# STM32F103.net
KiCad netlist of a schematic drawn in Altium Designer
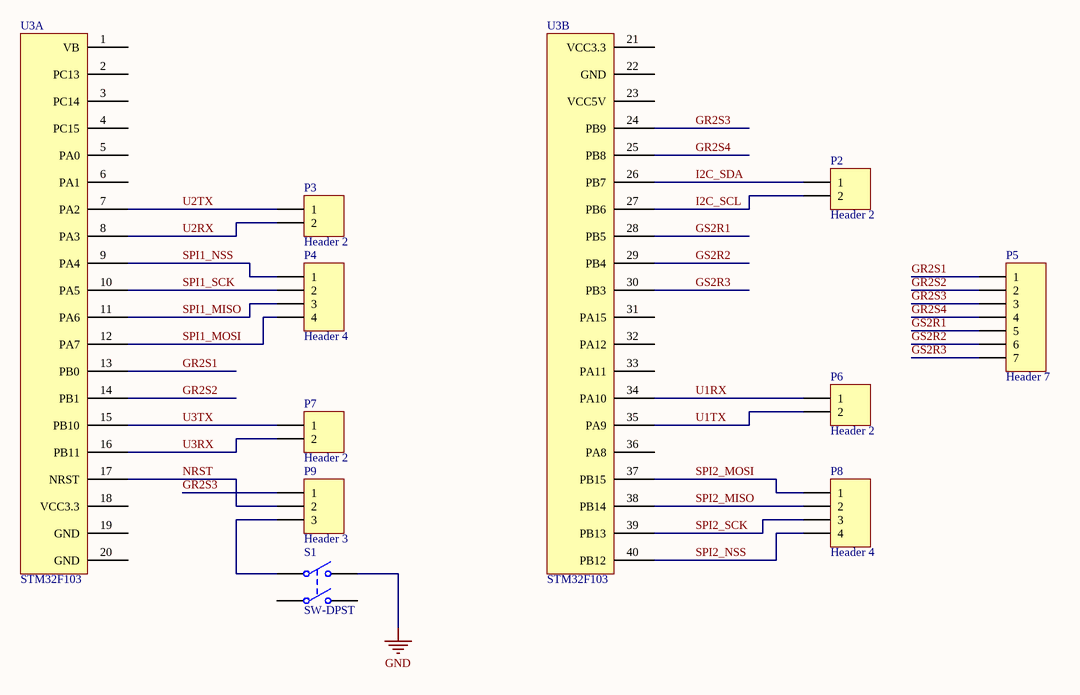
[diagram p0: STM32F103.SchDoc]

(export (version "E")
  (design (tool "Eeschema 10.0.6"))
  (components
    (comp (ref "P2")
      (value "Header 2")
      (footprint "HDR1X2")
      (description "Header, 2-Pin")
      (fields (field (name "PUBLISHER") "Altium Limited"))
      (libsource (lib "Miscellaneous Connectors") (part "Header 2"))
    )
    (comp (ref "P3")
      (value "Header 2")
      (footprint "HDR1X2")
      (description "Header, 2-Pin")
      (fields (field (name "PUBLISHER") "Altium Limited"))
      (libsource (lib "Miscellaneous Connectors") (part "Header 2"))
    )
    (comp (ref "P4")
      (value "Header 4")
      (footprint "HDR1X4")
      (description "Header, 4-Pin")
      (fields (field (name "PUBLISHER") "Altium Limited"))
      (libsource (lib "Miscellaneous Connectors") (part "Header 4"))
    )
    (comp (ref "P5")
      (value "Header 7")
      (footprint "HDR1X7")
      (description "Header, 7-Pin")
      (fields (field (name "PUBLISHER") "Altium Limited"))
      (libsource (lib "Miscellaneous Connectors") (part "Header 7"))
    )
    (comp (ref "P6")
      (value "Header 2")
      (footprint "HDR1X2")
      (description "Header, 2-Pin")
      (fields (field (name "PUBLISHER") "Altium Limited"))
      (libsource (lib "Miscellaneous Connectors") (part "Header 2"))
    )
    (comp (ref "P7")
      (value "Header 2")
      (footprint "HDR1X2")
      (description "Header, 2-Pin")
      (fields (field (name "PUBLISHER") "Altium Limited"))
      (libsource (lib "Miscellaneous Connectors") (part "Header 2"))
    )
    (comp (ref "P8")
      (value "Header 4")
      (footprint "HDR1X4")
      (description "Header, 4-Pin")
      (fields (field (name "PUBLISHER") "Altium Limited"))
      (libsource (lib "Miscellaneous Connectors") (part "Header 4"))
    )
    (comp (ref "P9")
      (value "Header 3")
      (footprint "HDR1X3")
      (description "Header, 3-Pin")
      (fields (field (name "PUBLISHER") "Altium Limited"))
      (libsource (lib "Miscellaneous Connectors") (part "Header 3"))
    )
    (comp (ref "S1")
      (value "SW-DPST")
      (footprint "SW6x6")
      (description "Double-Pole, Single-Throw Switch")
      (fields (field (name "PUBLISHER") "Altium Limited"))
      (libsource (lib "Miscellaneous Devices") (part "SW-DPST"))
    )
    (comp (ref "U3")
      (value "STM32F103")
      (footprint "STM32F103C8T6")
      (libsource (lib "CHK-I") (part "STM32F103C8T6"))
    )
  )
  (nets
    (net (code "1") (name "/GR2S1") (class "Default")
      (node (ref "P5") (pin "1") (pinfunction "1_1") (pintype "passive"))
      (node (ref "U3") (pin "13") (pinfunction "PB0_13") (pintype "passive"))
    )
    (net (code "2") (name "/GR2S2") (class "Default")
      (node (ref "P5") (pin "2") (pinfunction "2_2") (pintype "passive"))
      (node (ref "U3") (pin "14") (pinfunction "PB1_14") (pintype "passive"))
    )
    (net (code "3") (name "/GR2S3") (class "Default")
      (node (ref "P5") (pin "3") (pinfunction "3_3") (pintype "passive"))
      (node (ref "P9") (pin "1") (pinfunction "1_1") (pintype "passive"))
      (node (ref "U3") (pin "24") (pinfunction "PB9_24") (pintype "passive"))
    )
    (net (code "4") (name "/GR2S4") (class "Default")
      (node (ref "P5") (pin "4") (pinfunction "4_4") (pintype "passive"))
      (node (ref "U3") (pin "25") (pinfunction "PB8_25") (pintype "passive"))
    )
    (net (code "5") (name "/GS2R1") (class "Default")
      (node (ref "P5") (pin "5") (pinfunction "5_5") (pintype "passive"))
      (node (ref "U3") (pin "28") (pinfunction "PB5_28") (pintype "passive"))
    )
    (net (code "6") (name "/GS2R2") (class "Default")
      (node (ref "P5") (pin "6") (pinfunction "6_6") (pintype "passive"))
      (node (ref "U3") (pin "29") (pinfunction "PB4_29") (pintype "passive"))
    )
    (net (code "7") (name "/GS2R3") (class "Default")
      (node (ref "P5") (pin "7") (pinfunction "7_7") (pintype "passive"))
      (node (ref "U3") (pin "30") (pinfunction "PB3_30") (pintype "passive"))
    )
    (net (code "8") (name "/I2C_SCL") (class "Default")
      (node (ref "P2") (pin "2") (pinfunction "2_2") (pintype "passive"))
      (node (ref "U3") (pin "27") (pinfunction "PB6_27") (pintype "passive"))
    )
    (net (code "9") (name "/I2C_SDA") (class "Default")
      (node (ref "P2") (pin "1") (pinfunction "1_1") (pintype "passive"))
      (node (ref "U3") (pin "26") (pinfunction "PB7_26") (pintype "passive"))
    )
    (net (code "10") (name "/NRST") (class "Default")
      (node (ref "P9") (pin "2") (pinfunction "2_2") (pintype "passive"))
      (node (ref "U3") (pin "17") (pinfunction "NRST_17") (pintype "passive"))
    )
    (net (code "11") (name "/SPI1_MISO") (class "Default")
      (node (ref "P4") (pin "3") (pinfunction "3_3") (pintype "passive"))
      (node (ref "U3") (pin "11") (pinfunction "PA6_11") (pintype "passive"))
    )
    (net (code "12") (name "/SPI1_MOSI") (class "Default")
      (node (ref "P4") (pin "4") (pinfunction "4_4") (pintype "passive"))
      (node (ref "U3") (pin "12") (pinfunction "PA7_12") (pintype "passive"))
    )
    (net (code "13") (name "/SPI1_NSS") (class "Default")
      (node (ref "P4") (pin "1") (pinfunction "1_1") (pintype "passive"))
      (node (ref "U3") (pin "9") (pinfunction "PA4_9") (pintype "passive"))
    )
    (net (code "14") (name "/SPI1_SCK") (class "Default")
      (node (ref "P4") (pin "2") (pinfunction "2_2") (pintype "passive"))
      (node (ref "U3") (pin "10") (pinfunction "PA5_10") (pintype "passive"))
    )
    (net (code "15") (name "/SPI2_MISO") (class "Default")
      (node (ref "P8") (pin "2") (pinfunction "2_2") (pintype "passive"))
      (node (ref "U3") (pin "38") (pinfunction "PB14_38") (pintype "passive"))
    )
    (net (code "16") (name "/SPI2_MOSI") (class "Default")
      (node (ref "P8") (pin "1") (pinfunction "1_1") (pintype "passive"))
      (node (ref "U3") (pin "37") (pinfunction "PB15_37") (pintype "passive"))
    )
    (net (code "17") (name "/SPI2_NSS") (class "Default")
      (node (ref "P8") (pin "4") (pinfunction "4_4") (pintype "passive"))
      (node (ref "U3") (pin "40") (pinfunction "PB12_40") (pintype "passive"))
    )
    (net (code "18") (name "/SPI2_SCK") (class "Default")
      (node (ref "P8") (pin "3") (pinfunction "3_3") (pintype "passive"))
      (node (ref "U3") (pin "39") (pinfunction "PB13_39") (pintype "passive"))
    )
    (net (code "19") (name "/U1RX") (class "Default")
      (node (ref "P6") (pin "1") (pinfunction "1_1") (pintype "passive"))
      (node (ref "U3") (pin "34") (pinfunction "PA10_34") (pintype "passive"))
    )
    (net (code "20") (name "/U1TX") (class "Default")
      (node (ref "P6") (pin "2") (pinfunction "2_2") (pintype "passive"))
      (node (ref "U3") (pin "35") (pinfunction "PA9_35") (pintype "passive"))
    )
    (net (code "21") (name "/U2RX") (class "Default")
      (node (ref "P3") (pin "2") (pinfunction "2_2") (pintype "passive"))
      (node (ref "U3") (pin "8") (pinfunction "PA3_8") (pintype "passive"))
    )
    (net (code "22") (name "/U2TX") (class "Default")
      (node (ref "P3") (pin "1") (pinfunction "1_1") (pintype "passive"))
      (node (ref "U3") (pin "7") (pinfunction "PA2_7") (pintype "passive"))
    )
    (net (code "23") (name "/U3RX") (class "Default")
      (node (ref "P7") (pin "2") (pinfunction "2_2") (pintype "passive"))
      (node (ref "U3") (pin "16") (pinfunction "PB11_16") (pintype "passive"))
    )
    (net (code "24") (name "/U3TX") (class "Default")
      (node (ref "P7") (pin "1") (pinfunction "1_1") (pintype "passive"))
      (node (ref "U3") (pin "15") (pinfunction "PB10_15") (pintype "passive"))
    )
    (net (code "25") (name "GND") (class "Default")
      (node (ref "S1") (pin "2") (pinfunction "NO1_2") (pintype "passive"))
    )
    (net (code "26") (name "Net-(S1-COMMON1)") (class "Default")
      (node (ref "P9") (pin "3") (pinfunction "3_3") (pintype "passive"))
      (node (ref "S1") (pin "1") (pinfunction "COMMON1_1") (pintype "passive"))
    )
    (net (code "27") (name "unconnected-(S1-COMMON2-Pad3)") (class "Default")
      (node (ref "S1") (pin "3") (pinfunction "COMMON2_3") (pintype "passive"))
    )
    (net (code "28") (name "unconnected-(S1-NO2-Pad4)") (class "Default")
      (node (ref "S1") (pin "4") (pinfunction "NO2_4") (pintype "passive"))
    )
    (net (code "29") (name "unconnected-(U3A-GND-Pad19)") (class "Default")
      (node (ref "U3") (pin "19") (pinfunction "GND_19") (pintype "passive"))
    )
    (net (code "30") (name "unconnected-(U3A-GND-Pad20)") (class "Default")
      (node (ref "U3") (pin "20") (pinfunction "GND_20") (pintype "passive"))
    )
    (net (code "31") (name "unconnected-(U3A-PA0-Pad5)") (class "Default")
      (node (ref "U3") (pin "5") (pinfunction "PA0_5") (pintype "passive"))
    )
    (net (code "32") (name "unconnected-(U3A-PA1-Pad6)") (class "Default")
      (node (ref "U3") (pin "6") (pinfunction "PA1_6") (pintype "passive"))
    )
    (net (code "33") (name "unconnected-(U3A-PC13-Pad2)") (class "Default")
      (node (ref "U3") (pin "2") (pinfunction "PC13_2") (pintype "passive"))
    )
    (net (code "34") (name "unconnected-(U3A-PC14-Pad3)") (class "Default")
      (node (ref "U3") (pin "3") (pinfunction "PC14_3") (pintype "passive"))
    )
    (net (code "35") (name "unconnected-(U3A-PC15-Pad4)") (class "Default")
      (node (ref "U3") (pin "4") (pinfunction "PC15_4") (pintype "passive"))
    )
    (net (code "36") (name "unconnected-(U3A-VB-Pad1)") (class "Default")
      (node (ref "U3") (pin "1") (pinfunction "VB_1") (pintype "passive"))
    )
    (net (code "37") (name "unconnected-(U3A-VCC3.3-Pad18)") (class "Default")
      (node (ref "U3") (pin "18") (pinfunction "VCC3.3_18") (pintype "passive"))
    )
    (net (code "38") (name "unconnected-(U3B-GND-Pad22)") (class "Default")
      (node (ref "U3") (pin "22") (pinfunction "GND_22") (pintype "passive"))
    )
    (net (code "39") (name "unconnected-(U3B-PA8-Pad36)") (class "Default")
      (node (ref "U3") (pin "36") (pinfunction "PA8_36") (pintype "passive"))
    )
    (net (code "40") (name "unconnected-(U3B-PA11-Pad33)") (class "Default")
      (node (ref "U3") (pin "33") (pinfunction "PA11_33") (pintype "passive"))
    )
    (net (code "41") (name "unconnected-(U3B-PA12-Pad32)") (class "Default")
      (node (ref "U3") (pin "32") (pinfunction "PA12_32") (pintype "passive"))
    )
    (net (code "42") (name "unconnected-(U3B-PA15-Pad31)") (class "Default")
      (node (ref "U3") (pin "31") (pinfunction "PA15_31") (pintype "passive"))
    )
    (net (code "43") (name "unconnected-(U3B-VCC3.3-Pad21)") (class "Default")
      (node (ref "U3") (pin "21") (pinfunction "VCC3.3_21") (pintype "passive"))
    )
    (net (code "44") (name "unconnected-(U3B-VCC5V-Pad23)") (class "Default")
      (node (ref "U3") (pin "23") (pinfunction "VCC5V_23") (pintype "passive"))
    )
  )
)
